# communication.net
KiCad netlist of a schematic drawn in Altium Designer
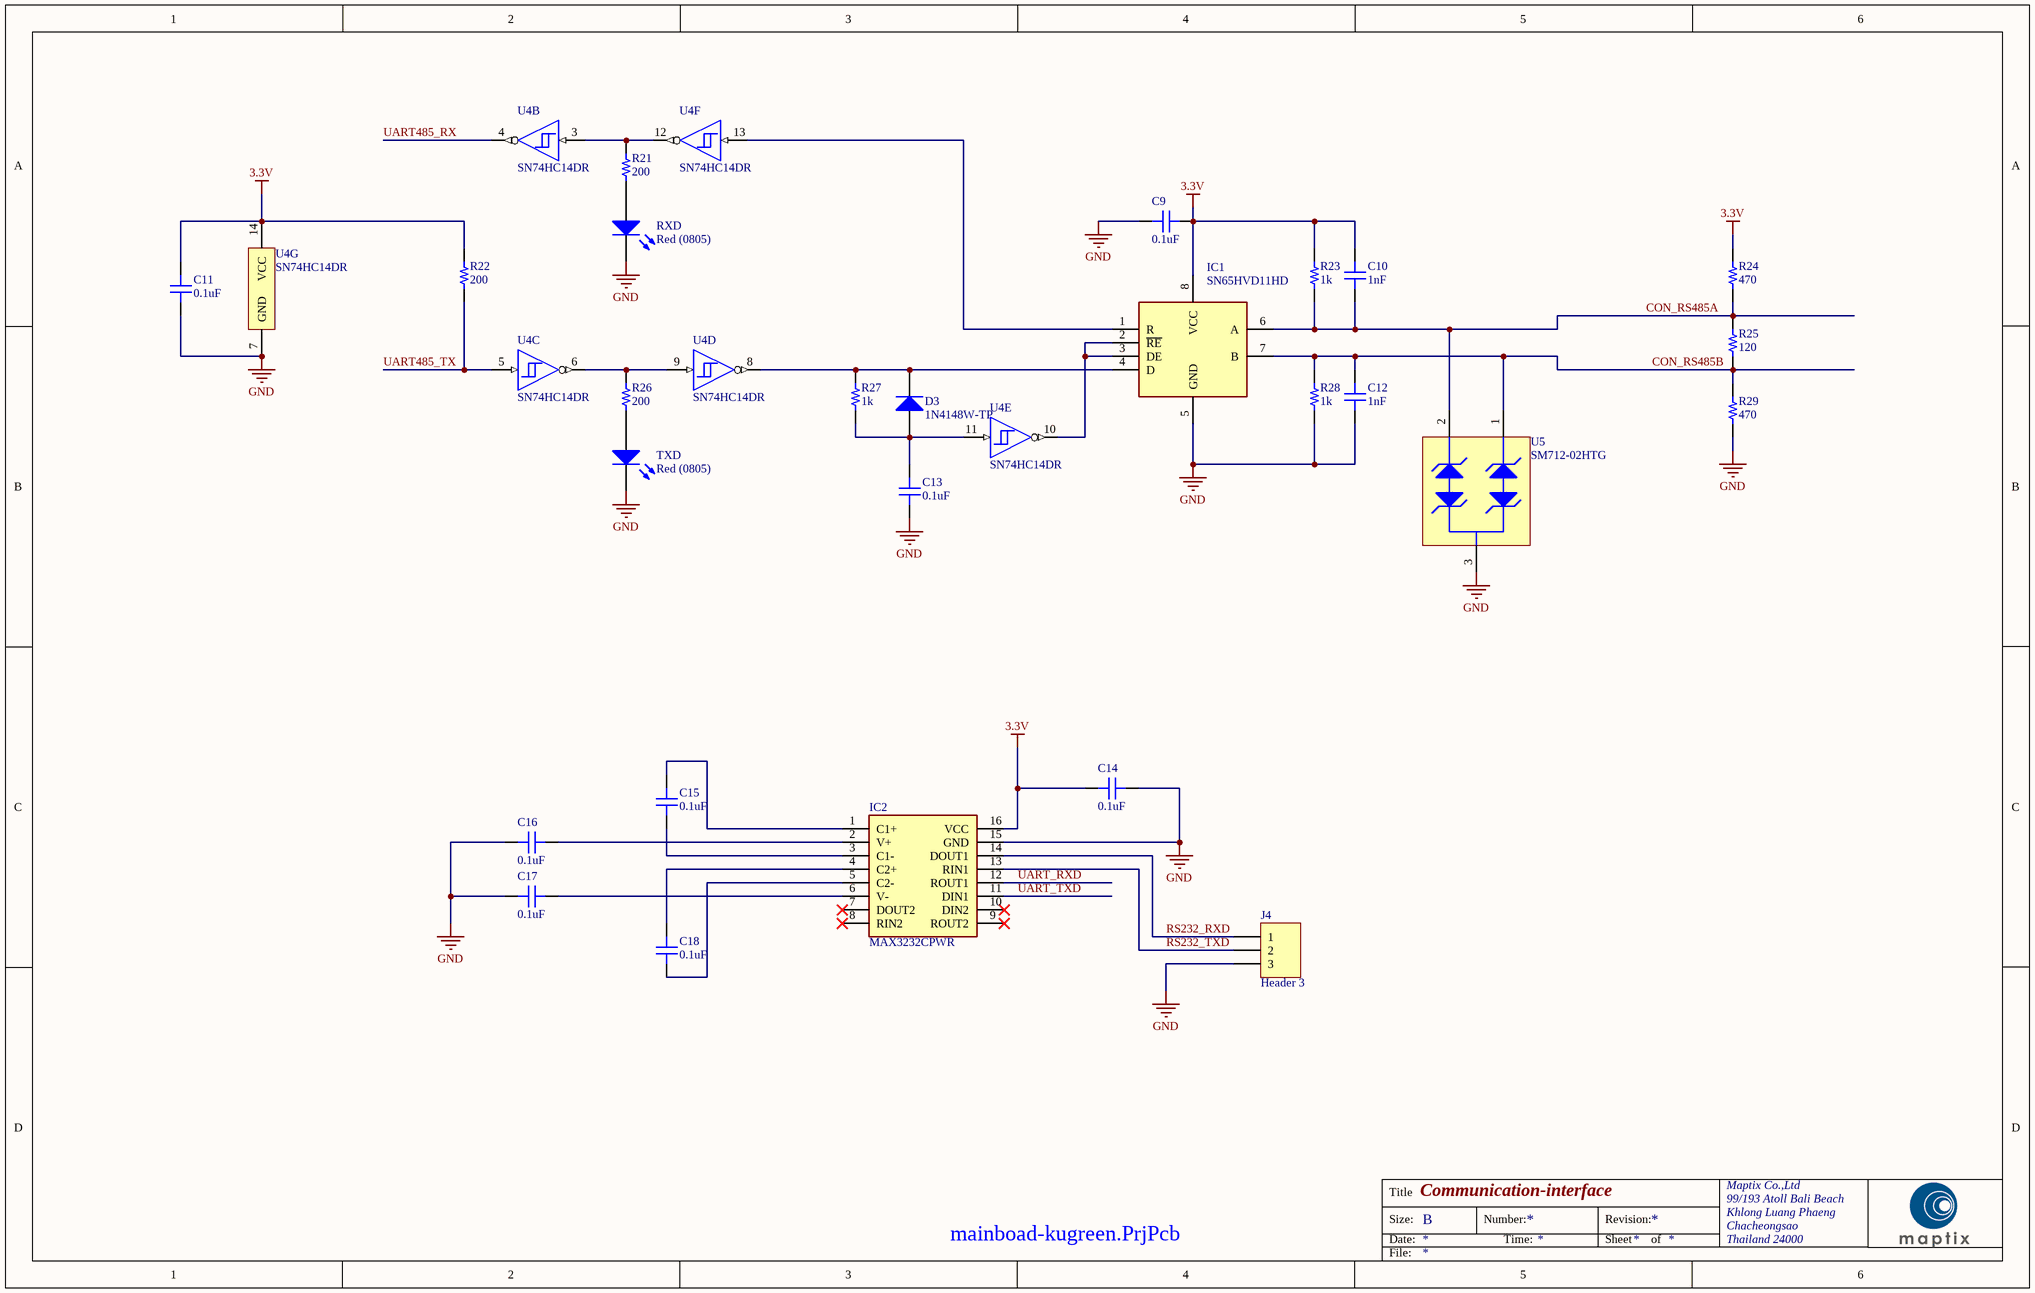
[diagram p0: communication.SchDoc]

(export (version "E")
  (design (tool "Eeschema 10.0.6"))
  (components
    (comp (ref "C9")
      (value "0.1uF")
      (footprint "CAP 0603_1608")
      (description "CAP CERAMIC 50V X7R 0603")
      (fields
        (field (name "PART NUMBER") "VJ0603Y332JXACW1BC")
        (field (name "MANUFACTURER") "Vishay Vitramon")
      )
      (libsource (lib "Celestial Altium Library - altium_library") (part "Capacitor"))
    )
    (comp (ref "C10")
      (value "1nF")
      (footprint "CAP 0603_1608")
      (description "CAP CERAMIC 50V X7R 0603")
      (fields
        (field (name "PART NUMBER") "VJ0603Y332JXACW1BC")
        (field (name "MANUFACTURER") "Vishay Vitramon")
      )
      (libsource (lib "Celestial Altium Library - altium_library") (part "Capacitor"))
    )
    (comp (ref "C11")
      (value "0.1uF")
      (footprint "CAP 0603_1608")
      (description "CAP CERAMIC 50V X7R 0603")
      (fields
        (field (name "PART NUMBER") "VJ0603Y332JXACW1BC")
        (field (name "MANUFACTURER") "Vishay Vitramon")
      )
      (libsource (lib "Celestial Altium Library - altium_library") (part "Capacitor"))
    )
    (comp (ref "C12")
      (value "1nF")
      (footprint "CAP 0603_1608")
      (description "CAP CERAMIC 50V X7R 0603")
      (fields
        (field (name "PART NUMBER") "VJ0603Y332JXACW1BC")
        (field (name "MANUFACTURER") "Vishay Vitramon")
      )
      (libsource (lib "Celestial Altium Library - altium_library") (part "Capacitor"))
    )
    (comp (ref "C13")
      (value "0.1uF")
      (footprint "CAP 0603_1608")
      (description "CAP CERAMIC 50V X7R 0603")
      (fields
        (field (name "PART NUMBER") "VJ0603Y332JXACW1BC")
        (field (name "MANUFACTURER") "Vishay Vitramon")
      )
      (libsource (lib "Celestial Altium Library - altium_library") (part "Capacitor"))
    )
    (comp (ref "C14")
      (value "0.1uF")
      (footprint "CAP 0603_1608")
      (description "CAP CERAMIC 50V X7R 0603")
      (fields
        (field (name "PART NUMBER") "VJ0603Y332JXACW1BC")
        (field (name "MANUFACTURER") "Vishay Vitramon")
      )
      (libsource (lib "Celestial Altium Library - altium_library") (part "Capacitor"))
    )
    (comp (ref "C15")
      (value "0.1uF")
      (footprint "CAP 0603_1608")
      (description "CAP CERAMIC 50V X7R 0603")
      (fields
        (field (name "PART NUMBER") "VJ0603Y332JXACW1BC")
        (field (name "MANUFACTURER") "Vishay Vitramon")
      )
      (libsource (lib "Celestial Altium Library - altium_library") (part "Capacitor"))
    )
    (comp (ref "C16")
      (value "0.1uF")
      (footprint "CAP 0603_1608")
      (description "CAP CERAMIC 50V X7R 0603")
      (fields
        (field (name "PART NUMBER") "VJ0603Y332JXACW1BC")
        (field (name "MANUFACTURER") "Vishay Vitramon")
      )
      (libsource (lib "Celestial Altium Library - altium_library") (part "Capacitor"))
    )
    (comp (ref "C17")
      (value "0.1uF")
      (footprint "CAP 0603_1608")
      (description "CAP CERAMIC 50V X7R 0603")
      (fields
        (field (name "PART NUMBER") "VJ0603Y332JXACW1BC")
        (field (name "MANUFACTURER") "Vishay Vitramon")
      )
      (libsource (lib "Celestial Altium Library - altium_library") (part "Capacitor"))
    )
    (comp (ref "C18")
      (value "0.1uF")
      (footprint "CAP 0603_1608")
      (description "CAP CERAMIC 50V X7R 0603")
      (fields
        (field (name "PART NUMBER") "VJ0603Y332JXACW1BC")
        (field (name "MANUFACTURER") "Vishay Vitramon")
      )
      (libsource (lib "Celestial Altium Library - altium_library") (part "Capacitor"))
    )
    (comp (ref "D3")
      (value "1N4148W-TP")
      (footprint "MCC-SOD123_V")
      (description "High Speed Switching Diode, 400 mW, 150 mA, -65 to 150 degC, 2-Pin SOD123, RoHS, Tape and Reel")
      (fields (field (name "MANUFACTURER") "Micro Commercial Components"))
      (libsource (lib "Altium Content Vault") (part "D-AK-2"))
    )
    (comp (ref "IC1")
      (value "SN65HVD11HD")
      (footprint "SamacSys:SOIC127P600X175-8N")
      (description "Integrated Circuit")
      (fields (field (name "MOUSER PART NUMBER") "595-SN65HVD11HD"))
      (libsource (lib "SamacSys") (part "SN65HVD11HD"))
    )
    (comp (ref "IC2")
      (value "MAX3232CPWR")
      (footprint "SamacSys:SOP65P640X120-16N")
      (description "Integrated Circuit")
      (fields (field (name "MOUSER PART NUMBER") "595-MAX3232CPWR"))
      (libsource (lib "*") (part "MAX3232CPWR"))
    )
    (comp (ref "J4")
      (value "Header 3")
      (footprint "HDR1X3")
      (description "Header, 3-Pin")
      (fields (field (name "PUBLISHER") "Altium Limited"))
      (libsource (lib "Miscellaneous Connectors") (part "Header 3"))
    )
    (comp (ref "R21")
      (value "200")
      (footprint "RES 0603_1608")
      (description "Resistor")
      (fields (field (name "PART NUMBER") "CRCW060329K4FKEA") (field (name "MANUFACTURER") "Vishay Dale"))
      (libsource (lib "Celestial Altium Library - altium_library") (part "Resistor"))
    )
    (comp (ref "R22")
      (value "200")
      (footprint "RES 0603_1608")
      (description "Resistor")
      (fields (field (name "PART NUMBER") "CRCW060329K4FKEA") (field (name "MANUFACTURER") "Vishay Dale"))
      (libsource (lib "Celestial Altium Library - altium_library") (part "Resistor"))
    )
    (comp (ref "R23")
      (value "1k")
      (footprint "RES 0603_1608")
      (description "Resistor")
      (fields (field (name "PART NUMBER") "CRCW060329K4FKEA") (field (name "MANUFACTURER") "Vishay Dale"))
      (libsource (lib "Celestial Altium Library - altium_library") (part "Resistor"))
    )
    (comp (ref "R24")
      (value "470")
      (footprint "RES 0603_1608")
      (description "Resistor")
      (fields (field (name "PART NUMBER") "CRCW060329K4FKEA") (field (name "MANUFACTURER") "Vishay Dale"))
      (libsource (lib "Celestial Altium Library - altium_library") (part "Resistor"))
    )
    (comp (ref "R25")
      (value "120")
      (footprint "RES 0603_1608")
      (description "Resistor")
      (fields (field (name "PART NUMBER") "CRCW060329K4FKEA") (field (name "MANUFACTURER") "Vishay Dale"))
      (libsource (lib "Celestial Altium Library - altium_library") (part "Resistor"))
    )
    (comp (ref "R26")
      (value "200")
      (footprint "RES 0603_1608")
      (description "Resistor")
      (fields (field (name "PART NUMBER") "CRCW060329K4FKEA") (field (name "MANUFACTURER") "Vishay Dale"))
      (libsource (lib "Celestial Altium Library - altium_library") (part "Resistor"))
    )
    (comp (ref "R27")
      (value "1k")
      (footprint "RES 0603_1608")
      (description "Resistor")
      (fields (field (name "PART NUMBER") "CRCW060329K4FKEA") (field (name "MANUFACTURER") "Vishay Dale"))
      (libsource (lib "Celestial Altium Library - altium_library") (part "Resistor"))
    )
    (comp (ref "R28")
      (value "1k")
      (footprint "RES 0603_1608")
      (description "Resistor")
      (fields (field (name "PART NUMBER") "CRCW060329K4FKEA") (field (name "MANUFACTURER") "Vishay Dale"))
      (libsource (lib "Celestial Altium Library - altium_library") (part "Resistor"))
    )
    (comp (ref "R29")
      (value "470")
      (footprint "RES 0603_1608")
      (description "Resistor")
      (fields (field (name "PART NUMBER") "CRCW060329K4FKEA") (field (name "MANUFACTURER") "Vishay Dale"))
      (libsource (lib "Celestial Altium Library - altium_library") (part "Resistor"))
    )
    (comp (ref "RXD")
      (value "Red (0805)")
      (footprint "0805_A")
      (description "SMD mono-color Chip LED, WL-SMCW, Green")
      (fields (field (name "PARTNUMBER") "150080GS75000") (field (name "MANUFACTURER") "Wuerth Elektronik"))
      (libsource (lib "Altium Content Vault") (part "WE-LED_K1A2-2"))
    )
    (comp (ref "TXD")
      (value "Red (0805)")
      (footprint "0805_A")
      (description "SMD mono-color Chip LED, WL-SMCW, Green")
      (fields (field (name "PARTNUMBER") "150080GS75000") (field (name "MANUFACTURER") "Wuerth Elektronik"))
      (libsource (lib "Altium Content Vault") (part "WE-LED_K1A2-2"))
    )
    (comp (ref "U4")
      (value "SN74HC14DR")
      (footprint "D0014A_N")
      (description "Hex Schmitt-Trigger Inverters, D0014A, LARGE T&R")
      (fields
        (field (name "MANUFACTURER") "Texas Instruments")
        (field (name "GENERIC PART NUMBER") "SN74HC14")
      )
      (libsource (lib "Altium Content Vault") (part "TI-CD_SNX4XXXXXX4X_19A-14-SCHMITT"))
    )
    (comp (ref "U5")
      (value "SM712-02HTG")
      (footprint "LFUS-SOT23-3_V")
      (description "TVS Diode Array, 600 W, 12 V, -40 to 125 degC, 3-Pin SOT23, RoHS, Tape and Reel")
      (fields (field (name "MANUFACTURER") "Littelfuse"))
      (libsource (lib "Altium Content Vault") (part "LFUS-SM712-SOT23-3"))
    )
  )
  (nets
    (net (code "1") (name "/CON_RS485A") (class "Default")
      (node (ref "C10") (pin "1") (pinfunction "1_1") (pintype "passive"))
      (node (ref "IC1") (pin "6") (pinfunction "A_6") (pintype "passive"))
      (node (ref "R23") (pin "1") (pinfunction "1_1") (pintype "passive"))
      (node (ref "R24") (pin "1") (pinfunction "1_1") (pintype "passive"))
      (node (ref "R25") (pin "2") (pinfunction "2_2") (pintype "passive"))
      (node (ref "U5") (pin "2") (pinfunction "2_2") (pintype "passive"))
    )
    (net (code "2") (name "/CON_RS485B") (class "Default")
      (node (ref "C12") (pin "2") (pinfunction "2_2") (pintype "passive"))
      (node (ref "IC1") (pin "7") (pinfunction "B_7") (pintype "passive"))
      (node (ref "R25") (pin "1") (pinfunction "1_1") (pintype "passive"))
      (node (ref "R28") (pin "2") (pinfunction "2_2") (pintype "passive"))
      (node (ref "R29") (pin "2") (pinfunction "2_2") (pintype "passive"))
      (node (ref "U5") (pin "1") (pinfunction "1_1") (pintype "passive"))
    )
    (net (code "3") (name "/RS232_RXD") (class "Default")
      (node (ref "IC2") (pin "14") (pinfunction "DOUT1_14") (pintype "passive"))
      (node (ref "J4") (pin "1") (pinfunction "1_1") (pintype "passive"))
    )
    (net (code "4") (name "/RS232_TXD") (class "Default")
      (node (ref "IC2") (pin "13") (pinfunction "RIN1_13") (pintype "passive"))
      (node (ref "J4") (pin "2") (pinfunction "2_2") (pintype "passive"))
    )
    (net (code "5") (name "/UART485_RX") (class "Default")
      (node (ref "U4") (pin "4") (pinfunction "~{2Y}_4") (pintype "output"))
    )
    (net (code "6") (name "/UART485_TX") (class "Default")
      (node (ref "R22") (pin "1") (pinfunction "1_1") (pintype "passive"))
      (node (ref "U4") (pin "5") (pinfunction "3A_5") (pintype "input"))
    )
    (net (code "7") (name "/UART_RXD") (class "Default")
      (node (ref "IC2") (pin "12") (pinfunction "ROUT1_12") (pintype "passive"))
    )
    (net (code "8") (name "/UART_TXD") (class "Default")
      (node (ref "IC2") (pin "11") (pinfunction "DIN1_11") (pintype "passive"))
    )
    (net (code "9") (name "3.3V") (class "Default")
      (node (ref "C10") (pin "2") (pinfunction "2_2") (pintype "passive"))
      (node (ref "C11") (pin "2") (pinfunction "2_2") (pintype "passive"))
      (node (ref "C14") (pin "1") (pinfunction "1_1") (pintype "passive"))
      (node (ref "C9") (pin "2") (pinfunction "2_2") (pintype "passive"))
      (node (ref "IC1") (pin "8") (pinfunction "VCC_8") (pintype "passive"))
      (node (ref "IC2") (pin "16") (pinfunction "VCC_16") (pintype "passive"))
      (node (ref "R22") (pin "2") (pinfunction "2_2") (pintype "passive"))
      (node (ref "R23") (pin "2") (pinfunction "2_2") (pintype "passive"))
      (node (ref "R24") (pin "2") (pinfunction "2_2") (pintype "passive"))
      (node (ref "U4") (pin "14") (pinfunction "VCC_14") (pintype "power_in"))
    )
    (net (code "10") (name "GND") (class "Default")
      (node (ref "C11") (pin "1") (pinfunction "1_1") (pintype "passive"))
      (node (ref "C12") (pin "1") (pinfunction "1_1") (pintype "passive"))
      (node (ref "C13") (pin "1") (pinfunction "1_1") (pintype "passive"))
      (node (ref "C14") (pin "2") (pinfunction "2_2") (pintype "passive"))
      (node (ref "C16") (pin "1") (pinfunction "1_1") (pintype "passive"))
      (node (ref "C17") (pin "1") (pinfunction "1_1") (pintype "passive"))
      (node (ref "C9") (pin "1") (pinfunction "1_1") (pintype "passive"))
      (node (ref "IC1") (pin "5") (pinfunction "GND_5") (pintype "passive"))
      (node (ref "IC2") (pin "15") (pinfunction "GND_15") (pintype "passive"))
      (node (ref "J4") (pin "3") (pinfunction "3_3") (pintype "passive"))
      (node (ref "R28") (pin "1") (pinfunction "1_1") (pintype "passive"))
      (node (ref "R29") (pin "1") (pinfunction "1_1") (pintype "passive"))
      (node (ref "RXD") (pin "1") (pinfunction "K_1") (pintype "passive"))
      (node (ref "TXD") (pin "1") (pinfunction "K_1") (pintype "passive"))
      (node (ref "U4") (pin "7") (pinfunction "GND_7") (pintype "power_in"))
      (node (ref "U5") (pin "3") (pinfunction "3_3") (pintype "passive"))
    )
    (net (code "11") (name "Net-(D3-A)") (class "Default")
      (node (ref "C13") (pin "2") (pinfunction "2_2") (pintype "passive"))
      (node (ref "D3") (pin "1") (pinfunction "A_1") (pintype "passive"))
      (node (ref "R27") (pin "1") (pinfunction "1_1") (pintype "passive"))
      (node (ref "U4") (pin "11") (pinfunction "5A_11") (pintype "input"))
    )
    (net (code "12") (name "Net-(D3-K)") (class "Default")
      (node (ref "D3") (pin "2") (pinfunction "K_2") (pintype "passive"))
      (node (ref "IC1") (pin "4") (pinfunction "D_4") (pintype "passive"))
      (node (ref "R27") (pin "2") (pinfunction "2_2") (pintype "passive"))
      (node (ref "U4") (pin "8") (pinfunction "~{4Y}_8") (pintype "output"))
    )
    (net (code "13") (name "Net-(IC1-DE)") (class "Default")
      (node (ref "IC1") (pin "2") (pinfunction "~{RE}_2") (pintype "passive"))
      (node (ref "IC1") (pin "3") (pinfunction "DE_3") (pintype "passive"))
      (node (ref "U4") (pin "10") (pinfunction "~{5Y}_10") (pintype "output"))
    )
    (net (code "14") (name "Net-(IC1-R)") (class "Default")
      (node (ref "IC1") (pin "1") (pinfunction "R_1") (pintype "passive"))
      (node (ref "U4") (pin "13") (pinfunction "6A_13") (pintype "input"))
    )
    (net (code "15") (name "Net-(IC2-C1+)") (class "Default")
      (node (ref "C15") (pin "1") (pinfunction "1_1") (pintype "passive"))
      (node (ref "IC2") (pin "1") (pinfunction "C1+_1") (pintype "passive"))
    )
    (net (code "16") (name "Net-(IC2-C1-)") (class "Default")
      (node (ref "C15") (pin "2") (pinfunction "2_2") (pintype "passive"))
      (node (ref "IC2") (pin "3") (pinfunction "C1-_3") (pintype "passive"))
    )
    (net (code "17") (name "Net-(IC2-C2+)") (class "Default")
      (node (ref "C18") (pin "1") (pinfunction "1_1") (pintype "passive"))
      (node (ref "IC2") (pin "4") (pinfunction "C2+_4") (pintype "passive"))
    )
    (net (code "18") (name "Net-(IC2-C2-)") (class "Default")
      (node (ref "C18") (pin "2") (pinfunction "2_2") (pintype "passive"))
      (node (ref "IC2") (pin "5") (pinfunction "C2-_5") (pintype "passive"))
    )
    (net (code "19") (name "Net-(IC2-V+)") (class "Default")
      (node (ref "C16") (pin "2") (pinfunction "2_2") (pintype "passive"))
      (node (ref "IC2") (pin "2") (pinfunction "V+_2") (pintype "passive"))
    )
    (net (code "20") (name "Net-(IC2-V-)") (class "Default")
      (node (ref "C17") (pin "2") (pinfunction "2_2") (pintype "passive"))
      (node (ref "IC2") (pin "6") (pinfunction "V-_6") (pintype "passive"))
    )
    (net (code "21") (name "Net-(RXD-A)") (class "Default")
      (node (ref "R21") (pin "1") (pinfunction "1_1") (pintype "passive"))
      (node (ref "RXD") (pin "2") (pinfunction "A_2") (pintype "passive"))
    )
    (net (code "22") (name "Net-(TXD-A)") (class "Default")
      (node (ref "R26") (pin "1") (pinfunction "1_1") (pintype "passive"))
      (node (ref "TXD") (pin "2") (pinfunction "A_2") (pintype "passive"))
    )
    (net (code "23") (name "Net-(U4B-2A)") (class "Default")
      (node (ref "R21") (pin "2") (pinfunction "2_2") (pintype "passive"))
      (node (ref "U4") (pin "12") (pinfunction "~{6Y}_12") (pintype "output"))
      (node (ref "U4") (pin "3") (pinfunction "2A_3") (pintype "input"))
    )
    (net (code "24") (name "Net-(U4C-~{3Y})") (class "Default")
      (node (ref "R26") (pin "2") (pinfunction "2_2") (pintype "passive"))
      (node (ref "U4") (pin "6") (pinfunction "~{3Y}_6") (pintype "output"))
      (node (ref "U4") (pin "9") (pinfunction "4A_9") (pintype "input"))
    )
    (net (code "25") (name "unconnected-(IC2-DIN2-Pad10)") (class "Default")
      (node (ref "IC2") (pin "10") (pinfunction "DIN2_10") (pintype "passive+no_connect"))
    )
    (net (code "26") (name "unconnected-(IC2-DOUT2-Pad7)") (class "Default")
      (node (ref "IC2") (pin "7") (pinfunction "DOUT2_7") (pintype "passive+no_connect"))
    )
    (net (code "27") (name "unconnected-(IC2-RIN2-Pad8)") (class "Default")
      (node (ref "IC2") (pin "8") (pinfunction "RIN2_8") (pintype "passive+no_connect"))
    )
    (net (code "28") (name "unconnected-(IC2-ROUT2-Pad9)") (class "Default")
      (node (ref "IC2") (pin "9") (pinfunction "ROUT2_9") (pintype "passive+no_connect"))
    )
  )
)
